# Nokia_1202_breakout.net
KiCad netlist of a schematic drawn in EAGLE
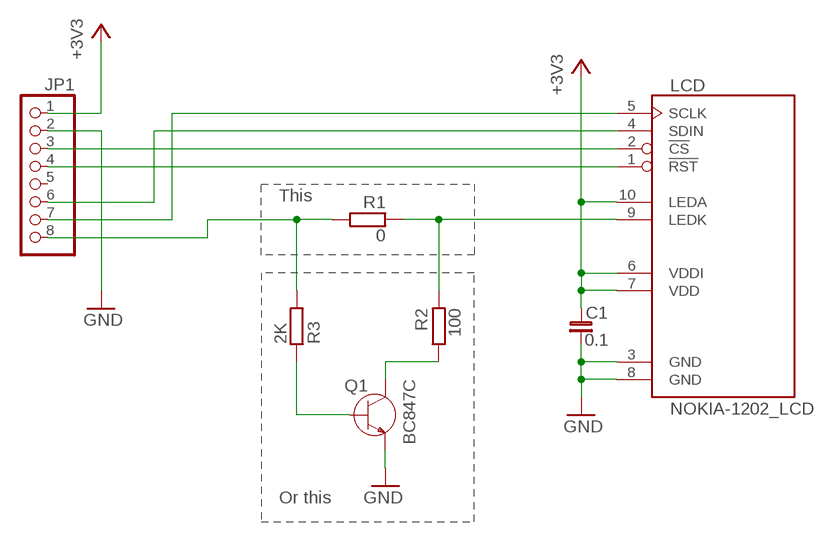
[diagram p0: schematic, sheet 1]

(export (version "E")
  (design (tool "Eeschema 10.0.6"))
  (components
    (comp (ref "C1")
      (value "0.1")
      (footprint "eagle-import:C0805")
      (libsource (lib "eagle-import") (part "C_0805"))
    )
    (comp (ref "JP1")
      (value "PINHD-1X8")
      (footprint "eagle-import:1X08")
      (libsource (lib "eagle-import") (part "PINHD-1X8"))
    )
    (comp (ref "LCD")
      (value "NOKIA-1202_LCD")
      (footprint "eagle-import:NOKIA-1202_LCD")
      (libsource (lib "eagle-import") (part "NOKIA-1202_LCD"))
    )
    (comp (ref "Q1")
      (value "BC847C")
      (footprint "eagle-import:SOT23")
      (libsource (lib "eagle-import") (part "BC847C"))
    )
    (comp (ref "R1")
      (value "0")
      (footprint "eagle-import:R0805")
      (libsource (lib "eagle-import") (part "R_0805"))
    )
    (comp (ref "R2")
      (value "100")
      (footprint "eagle-import:R0805")
      (libsource (lib "eagle-import") (part "R_0805"))
    )
    (comp (ref "R3")
      (value "2K")
      (footprint "eagle-import:R0805")
      (libsource (lib "eagle-import") (part "R_0805"))
    )
  )
  (nets
    (net (code "1") (name "+3V3") (class "Default")
      (node (ref "C1") (pin "1") (pinfunction "1_1") (pintype "passive"))
      (node (ref "JP1") (pin "1") (pinfunction "1_1") (pintype "passive"))
      (node (ref "LCD") (pin "10") (pinfunction "LEDA_10") (pintype "passive"))
      (node (ref "LCD") (pin "6") (pinfunction "VDDI_6") (pintype "power_in"))
      (node (ref "LCD") (pin "7") (pinfunction "VDD_7") (pintype "power_in"))
    )
    (net (code "2") (name "GND") (class "Default")
      (node (ref "C1") (pin "2") (pinfunction "2_2") (pintype "passive"))
      (node (ref "JP1") (pin "2") (pinfunction "2_2") (pintype "passive"))
      (node (ref "LCD") (pin "3") (pinfunction "GND_3") (pintype "power_in"))
      (node (ref "LCD") (pin "8") (pinfunction "GND_8") (pintype "power_in"))
      (node (ref "Q1") (pin "2") (pinfunction "E_2") (pintype "passive"))
    )
    (net (code "3") (name "Net-(JP1-Pad8)") (class "Default")
      (node (ref "JP1") (pin "8") (pinfunction "8_8") (pintype "passive"))
      (node (ref "R1") (pin "2") (pinfunction "2_2") (pintype "passive"))
      (node (ref "R3") (pin "2") (pinfunction "2_2") (pintype "passive"))
    )
    (net (code "4") (name "Net-(LCD-LEDK)") (class "Default")
      (node (ref "LCD") (pin "9") (pinfunction "LEDK_9") (pintype "passive"))
      (node (ref "R1") (pin "1") (pinfunction "1_1") (pintype "passive"))
      (node (ref "R2") (pin "1") (pinfunction "1_1") (pintype "passive"))
    )
    (net (code "5") (name "Net-(LCD-SCLK)") (class "Default")
      (node (ref "JP1") (pin "7") (pinfunction "7_7") (pintype "passive"))
      (node (ref "LCD") (pin "5") (pinfunction "SCLK_5") (pintype "input"))
    )
    (net (code "6") (name "Net-(LCD-SDIN)") (class "Default")
      (node (ref "JP1") (pin "6") (pinfunction "6_6") (pintype "passive"))
      (node (ref "LCD") (pin "4") (pinfunction "SDIN_4") (pintype "input"))
    )
    (net (code "7") (name "Net-(LCD-~{CS})") (class "Default")
      (node (ref "JP1") (pin "3") (pinfunction "3_3") (pintype "passive"))
      (node (ref "LCD") (pin "2") (pinfunction "~{CS}_2") (pintype "input"))
    )
    (net (code "8") (name "Net-(LCD-~{RST})") (class "Default")
      (node (ref "JP1") (pin "4") (pinfunction "4_4") (pintype "passive"))
      (node (ref "LCD") (pin "1") (pinfunction "~{RST}_1") (pintype "input"))
    )
    (net (code "9") (name "Net-(Q1-B)") (class "Default")
      (node (ref "Q1") (pin "1") (pinfunction "B_1") (pintype "passive"))
      (node (ref "R3") (pin "1") (pinfunction "1_1") (pintype "passive"))
    )
    (net (code "10") (name "Net-(Q1-C)") (class "Default")
      (node (ref "Q1") (pin "3") (pinfunction "C_3") (pintype "passive"))
      (node (ref "R2") (pin "2") (pinfunction "2_2") (pintype "passive"))
    )
    (net (code "11") (name "unconnected-(JP1-Pad5)") (class "Default")
      (node (ref "JP1") (pin "5") (pinfunction "5_5") (pintype "passive"))
    )
  )
)
